# Power.net
KiCad netlist of a schematic drawn in Altium Designer
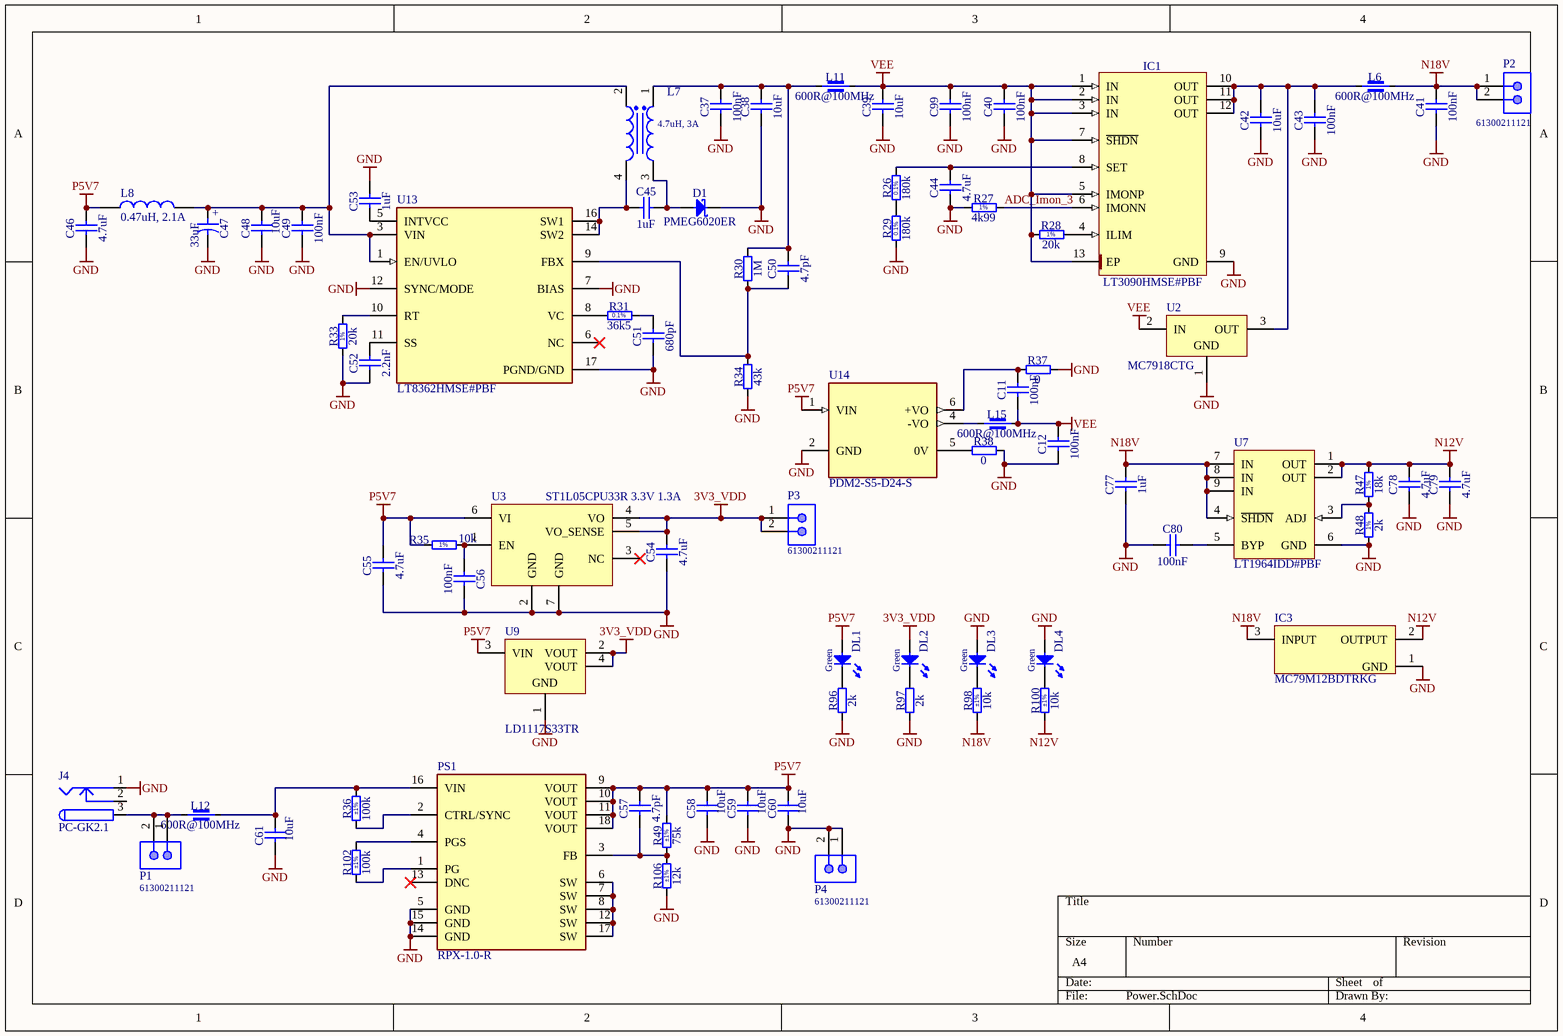
[diagram p0: Power.SchDoc]

(export (version "E")
  (design (tool "Eeschema 10.0.6"))
  (components
    (comp (ref "C11")
      (value "100nF")
      (footprint "CAPC1005X55N")
      (description "Non-polarised capacitor")
      (fields
        (field (name "PART NUMBER") "CC0402_100NF_16V_10%_X7R")
        (field (name "VOLTAGE") "16V")
        (field (name "AUTHOR") "CERN DEM JLC")
      )
      (libsource (lib "Capacitors") (part "Capacitor - non polarized"))
    )
    (comp (ref "C12")
      (value "100nF")
      (footprint "CAPC1005X55N")
      (description "Non-polarised capacitor")
      (fields
        (field (name "PART NUMBER") "CC0402_100NF_16V_10%_X7R")
        (field (name "VOLTAGE") "16V")
        (field (name "AUTHOR") "CERN DEM JLC")
      )
      (libsource (lib "Capacitors") (part "Capacitor - non polarized"))
    )
    (comp (ref "C37")
      (value "100nF")
      (footprint "CAPC1608X87N")
      (description "Non-polarised capacitor")
      (fields
        (field (name "PART NUMBER") "CC0603_100NF_50V_10%_X5R")
        (field (name "VOLTAGE") "50V")
        (field (name "AUTHOR") "CERN DEM MR")
      )
      (libsource (lib "Capacitors") (part "Capacitor - non polarized"))
    )
    (comp (ref "C38")
      (value "10uF")
      (footprint "CAPC3216X190N")
      (description "Non-polarised capacitor")
      (fields
        (field (name "PART NUMBER") "CC1206_10UF_35V_10%_X7R_YUDEN_GMJ316BB7106KLHT")
        (field (name "VOLTAGE") "35V")
        (field (name "AUTHOR") "CERN DEM BC")
      )
      (libsource (lib "Capacitors") (part "Capacitor - non polarized"))
    )
    (comp (ref "C39")
      (value "10uF")
      (footprint "CAPC3216X190N")
      (description "Non-polarised capacitor")
      (fields
        (field (name "PART NUMBER") "CC1206_10UF_35V_10%_X7R_YUDEN_GMJ316BB7106KLHT")
        (field (name "VOLTAGE") "35V")
        (field (name "AUTHOR") "CERN DEM BC")
      )
      (libsource (lib "Capacitors") (part "Capacitor - non polarized"))
    )
    (comp (ref "C40")
      (value "100nF")
      (footprint "CAPC1608X87N")
      (description "Non-polarised capacitor")
      (fields
        (field (name "PART NUMBER") "CC0603_100NF_50V_10%_X5R")
        (field (name "VOLTAGE") "50V")
        (field (name "AUTHOR") "CERN DEM MR")
      )
      (libsource (lib "Capacitors") (part "Capacitor - non polarized"))
    )
    (comp (ref "C41")
      (value "100nF")
      (footprint "CAPC1608X87N")
      (description "Non-polarised capacitor")
      (fields
        (field (name "PART NUMBER") "CC0603_100NF_50V_10%_X5R")
        (field (name "VOLTAGE") "50V")
        (field (name "AUTHOR") "CERN DEM MR")
      )
      (libsource (lib "Capacitors") (part "Capacitor - non polarized"))
    )
    (comp (ref "C42")
      (value "10uF")
      (footprint "CAPC3216X190N")
      (description "Non-polarised capacitor")
      (fields
        (field (name "PART NUMBER") "CC1206_10UF_35V_10%_X7R_YUDEN_GMJ316BB7106KLHT")
        (field (name "VOLTAGE") "35V")
        (field (name "AUTHOR") "CERN DEM BC")
      )
      (libsource (lib "Capacitors") (part "Capacitor - non polarized"))
    )
    (comp (ref "C43")
      (value "100nF")
      (footprint "CAPC1608X87N")
      (description "Non-polarised capacitor")
      (fields
        (field (name "PART NUMBER") "CC0603_100NF_50V_10%_X5R")
        (field (name "VOLTAGE") "50V")
        (field (name "AUTHOR") "CERN DEM MR")
      )
      (libsource (lib "Capacitors") (part "Capacitor - non polarized"))
    )
    (comp (ref "C44")
      (value "4.7uF")
      (footprint "CAPC1608X90N")
      (description "Non-polarised capacitor")
      (fields
        (field (name "PART NUMBER") "CC0603_4.7UF_25V_10%_X5R")
        (field (name "VOLTAGE") "25V")
        (field (name "AUTHOR") "CERN DEM JLC")
      )
      (libsource (lib "Capacitors") (part "Capacitor - non polarized"))
    )
    (comp (ref "C45")
      (value "1uF")
      (footprint "CAPC3216X140N")
      (description "Non-polarised capacitor")
      (fields
        (field (name "PART NUMBER") "CC1206_1UF_100V_10%_X7R")
        (field (name "VOLTAGE") "100V")
        (field (name "AUTHOR") "CERN DEM BC")
      )
      (libsource (lib "Capacitors") (part "Capacitor - non polarized"))
    )
    (comp (ref "C46")
      (value "4.7uF")
      (footprint "CAPC1608X90N")
      (description "Non-polarised capacitor")
      (fields
        (field (name "PART NUMBER") "CC0603_4.7UF_25V_10%_X5R")
        (field (name "VOLTAGE") "25V")
        (field (name "AUTHOR") "CERN DEM JLC")
      )
      (libsource (lib "Capacitors") (part "Capacitor - non polarized"))
    )
    (comp (ref "C47")
      (value "33uF")
      (footprint "CAPAE660X540N")
      (description "Polarised capacitor")
      (fields
        (field (name "PART NUMBER") "CAE660-540_33UF_35V_20%")
        (field (name "VOLTAGE") "35V")
        (field (name "AUTHOR") "CERN DEM JLC")
      )
      (libsource (lib "Capacitors") (part "Capacitor - polarized"))
    )
    (comp (ref "C48")
      (value "10uF")
      (footprint "CAPC3216X190N")
      (description "Non-polarised capacitor")
      (fields
        (field (name "PART NUMBER") "CC1206_10UF_35V_10%_X7R_YUDEN_GMJ316BB7106KLHT")
        (field (name "VOLTAGE") "35V")
        (field (name "AUTHOR") "CERN DEM BC")
      )
      (libsource (lib "Capacitors") (part "Capacitor - non polarized"))
    )
    (comp (ref "C49")
      (value "100nF")
      (footprint "CAPC1608X87N")
      (description "Non-polarised capacitor")
      (fields
        (field (name "PART NUMBER") "CC0603_100NF_50V_10%_X5R")
        (field (name "VOLTAGE") "50V")
        (field (name "AUTHOR") "CERN DEM MR")
      )
      (libsource (lib "Capacitors") (part "Capacitor - non polarized"))
    )
    (comp (ref "C50")
      (value "4.7pF")
      (footprint "CAPC1005X55N")
      (description "Non-polarised capacitor")
      (fields
        (field (name "PART NUMBER") "CC0402_4.7PF_50V_0.25PF_C0G")
        (field (name "VOLTAGE") "50V")
        (field (name "AUTHOR") "CERN DEM JLC")
      )
      (libsource (lib "Capacitors") (part "Capacitor - non polarized"))
    )
    (comp (ref "C51")
      (value "680pF")
      (footprint "CAPC1005X55N")
      (description "Non-polarised capacitor")
      (fields
        (field (name "PART NUMBER") "CC0402_680PF_50V_5%_X7R")
        (field (name "VOLTAGE") "50V")
        (field (name "AUTHOR") "CERN DEM JLC")
      )
      (libsource (lib "Capacitors") (part "Capacitor - non polarized"))
    )
    (comp (ref "C52")
      (value "2.2nF")
      (footprint "CAPC1005X55N")
      (description "Non-polarised capacitor")
      (fields
        (field (name "PART NUMBER") "CC0402_2.2NF_50V_10%_X7R")
        (field (name "VOLTAGE") "50V")
        (field (name "AUTHOR") "CERN DEM JLC")
      )
      (libsource (lib "Capacitors") (part "Capacitor - non polarized"))
    )
    (comp (ref "C53")
      (value "1uF")
      (footprint "CAPC1005X55N")
      (description "Non-polarised capacitor")
      (fields
        (field (name "PART NUMBER") "CC0402_1UF_16V_10%_X5R")
        (field (name "VOLTAGE") "16V")
        (field (name "AUTHOR") "CERN DEM JLC")
      )
      (libsource (lib "Capacitors") (part "Capacitor - non polarized"))
    )
    (comp (ref "C54")
      (value "4.7uF")
      (footprint "CAPC1709X95N")
      (description "Non-polarised capacitor")
      (fields
        (field (name "PART NUMBER") "CC0603_4.7UF_16V_10%_X5R")
        (field (name "VOLTAGE") "16V")
        (field (name "AUTHOR") "CERN DEM JLC")
      )
      (libsource (lib "Capacitors") (part "Capacitor - non polarized"))
    )
    (comp (ref "C55")
      (value "4.7uF")
      (footprint "CAPC1709X95N")
      (description "Non-polarised capacitor")
      (fields
        (field (name "PART NUMBER") "CC0603_4.7UF_16V_10%_X5R")
        (field (name "VOLTAGE") "16V")
        (field (name "AUTHOR") "CERN DEM JLC")
      )
      (libsource (lib "Capacitors") (part "Capacitor - non polarized"))
    )
    (comp (ref "C56")
      (value "100nF")
      (footprint "CAPC1005X55N")
      (description "Non-polarised capacitor")
      (fields
        (field (name "PART NUMBER") "CC0402_100NF_16V_10%_X5R")
        (field (name "VOLTAGE") "16V")
        (field (name "AUTHOR") "CERN DEM JLC")
      )
      (libsource (lib "Capacitors") (part "Capacitor - non polarized"))
    )
    (comp (ref "C57")
      (value "4.7pF")
      (footprint "CAPC1005X55N")
      (description "Non-polarised capacitor")
      (fields
        (field (name "PART NUMBER") "CC0402_4.7PF_50V_0.25PF_C0G")
        (field (name "VOLTAGE") "50V")
        (field (name "AUTHOR") "CERN DEM JLC")
      )
      (libsource (lib "Capacitors") (part "Capacitor - non polarized"))
    )
    (comp (ref "C58")
      (value "10uF")
      (footprint "CAPC3216X190N")
      (description "Non-polarised capacitor")
      (fields
        (field (name "PART NUMBER") "CC1206_10UF_35V_10%_X7R_YUDEN_GMJ316BB7106KLHT")
        (field (name "VOLTAGE") "35V")
        (field (name "AUTHOR") "CERN DEM BC")
      )
      (libsource (lib "Capacitors") (part "Capacitor - non polarized"))
    )
    (comp (ref "C59")
      (value "10uF")
      (footprint "CAPC3216X190N")
      (description "Non-polarised capacitor")
      (fields
        (field (name "PART NUMBER") "CC1206_10UF_35V_10%_X7R_YUDEN_GMJ316BB7106KLHT")
        (field (name "VOLTAGE") "35V")
        (field (name "AUTHOR") "CERN DEM BC")
      )
      (libsource (lib "Capacitors") (part "Capacitor - non polarized"))
    )
    (comp (ref "C60")
      (value "10uF")
      (footprint "CAPC3216X190N")
      (description "Non-polarised capacitor")
      (fields
        (field (name "PART NUMBER") "CC1206_10UF_35V_10%_X7R_YUDEN_GMJ316BB7106KLHT")
        (field (name "VOLTAGE") "35V")
        (field (name "AUTHOR") "CERN DEM BC")
      )
      (libsource (lib "Capacitors") (part "Capacitor - non polarized"))
    )
    (comp (ref "C61")
      (value "10uF")
      (footprint "CAPC3216X190N")
      (description "Non-polarised capacitor")
      (fields
        (field (name "PART NUMBER") "CC1206_10UF_35V_10%_X7R_YUDEN_GMJ316BB7106KLHT")
        (field (name "VOLTAGE") "35V")
        (field (name "AUTHOR") "CERN DEM BC")
      )
      (libsource (lib "Capacitors") (part "Capacitor - non polarized"))
    )
    (comp (ref "C77")
      (value "1uF")
      (footprint "CAPC1608X87N")
      (description "Non-polarised capacitor")
      (fields
        (field (name "PART NUMBER") "CC0603_1UF_25V_10%_X7R")
        (field (name "VOLTAGE") "25V")
        (field (name "AUTHOR") "CERN DEM JLC")
      )
      (libsource (lib "Capacitors") (part "Capacitor - non polarized"))
    )
    (comp (ref "C78")
      (value "4.7uF")
      (footprint "CAPC1709X95N")
      (description "Non-polarised capacitor")
      (fields
        (field (name "PART NUMBER") "CC0603_4.7UF_16V_10%_X5R")
        (field (name "VOLTAGE") "16V")
        (field (name "AUTHOR") "CERN DEM JLC")
      )
      (libsource (lib "Capacitors") (part "Capacitor - non polarized"))
    )
    (comp (ref "C79")
      (value "4.7uF")
      (footprint "CAPC1709X95N")
      (description "Non-polarised capacitor")
      (fields
        (field (name "PART NUMBER") "CC0603_4.7UF_16V_10%_X5R")
        (field (name "VOLTAGE") "16V")
        (field (name "AUTHOR") "CERN DEM JLC")
      )
      (libsource (lib "Capacitors") (part "Capacitor - non polarized"))
    )
    (comp (ref "C80")
      (value "100nF")
      (footprint "CAPC1005X55N")
      (description "Non-polarised capacitor")
      (fields
        (field (name "PART NUMBER") "CC0402_100NF_16V_10%_X7R")
        (field (name "VOLTAGE") "16V")
        (field (name "AUTHOR") "CERN DEM JLC")
      )
      (libsource (lib "Capacitors") (part "Capacitor - non polarized"))
    )
    (comp (ref "C99")
      (value "100nF")
      (footprint "CAPC1608X87N")
      (description "Non-polarised capacitor")
      (fields
        (field (name "PART NUMBER") "CC0603_100NF_50V_10%_X5R")
        (field (name "VOLTAGE") "50V")
        (field (name "AUTHOR") "CERN DEM MR")
      )
      (libsource (lib "Capacitors") (part "Capacitor - non polarized"))
    )
    (comp (ref "D1")
      (value "PMEG6020ER")
      (footprint "SODFL3517X110N")
      (description "Schottky Diode")
      (fields
        (field (name "VOLTAGE") "60V")
        (field (name "POWER") "2A")
        (field (name "AUTHOR") "CERN DEM JMW")
      )
      (libsource (lib "ICs And Semiconductors") (part "Diode Schottky"))
    )
    (comp (ref "DL1")
      (value "Green")
      (footprint "LED_OSRAM_LGL29K")
      (description "LED Green 1C 2A")
      (fields
        (field (name "PART NUMBER") "LED_OSRAM_LG L29K-G2J1-24-Z")
        (field (name "MANUFACTURER") "OSRAM")
        (field (name "AUTHOR") "CERN DEM JLC")
      )
      (libsource (lib "ICs And Semiconductors") (part "LED Green 1C 2A"))
    )
    (comp (ref "DL2")
      (value "Green")
      (footprint "LED_OSRAM_LGL29K")
      (description "LED Green 1C 2A")
      (fields
        (field (name "PART NUMBER") "LED_OSRAM_LG L29K-G2J1-24-Z")
        (field (name "MANUFACTURER") "OSRAM")
        (field (name "AUTHOR") "CERN DEM JLC")
      )
      (libsource (lib "ICs And Semiconductors") (part "LED Green 1C 2A"))
    )
    (comp (ref "DL3")
      (value "Green")
      (footprint "LED_OSRAM_LGL29K")
      (description "LED Green 1C 2A")
      (fields
        (field (name "PART NUMBER") "LED_OSRAM_LG L29K-G2J1-24-Z")
        (field (name "MANUFACTURER") "OSRAM")
        (field (name "AUTHOR") "CERN DEM JLC")
      )
      (libsource (lib "ICs And Semiconductors") (part "LED Green 1C 2A"))
    )
    (comp (ref "DL4")
      (value "Green")
      (footprint "LED_OSRAM_LGL29K")
      (description "LED Green 1C 2A")
      (fields
        (field (name "PART NUMBER") "LED_OSRAM_LG L29K-G2J1-24-Z")
        (field (name "MANUFACTURER") "OSRAM")
        (field (name "AUTHOR") "CERN DEM JLC")
      )
      (libsource (lib "ICs And Semiconductors") (part "LED Green 1C 2A"))
    )
    (comp (ref "IC1")
      (value "LT3090HMSE#PBF")
      (footprint "SOP65P490X110-13N-R175X294")
      (description "–36V, 600mA Negative Linear Regulator with Programmable Current Limit")
      (fields (field (name "MANUFACTURER") "LINEAR TECHNOLOGY") (field (name "AUTHOR") "CERN DEM JLC"))
      (libsource (lib "ICs And Semiconductors") (part "LT3090HMSE#PBF"))
    )
    (comp (ref "IC3")
      (value "MC79M12BDTRKG")
      (footprint "TO228P991X239-3N-R546X521")
      (libsource (lib "MG_lib_laptop") (part "MC79M12BDTRKG"))
    )
    (comp (ref "J4")
      (value "PC-GK2.1")
      (footprint "DC2020")
      (description "Low Voltage Power Supply Connector (maritex)")
      (fields (field (name "PUBLISHER") "Altium Limited"))
      (libsource (lib "LIBRARY_SCH") (part "CON_DC_JACK_TH"))
    )
    (comp (ref "L6")
      (value "600R@100MHz")
      (footprint "INDC2012X110N")
      (fields
        (field (name "PART NUMBER") "IND0805_WURTH_742792040")
        (field (name "POWER") "2A")
        (field (name "TOLERANCE") "±25%")
        (field (name "AUTHOR") "CERN DEM JLC")
      )
      (libsource (lib "Inductors & Transformers") (part "Ferrite Bead"))
    )
    (comp (ref "L7")
      (value "4.7uH, 3A")
      (footprint "WE-DD_1260")
      (description "WE-DD SMT Shielded Coupled Inductor, size 1260, 4.7uH, 3A")
      (fields
        (field (name "MANUFACTURER") "Wurth Elektronik")
        (field (name "MANUFACTURER PART NUMBER") "744871004")
      )
      (libsource (lib "744871470_Altium_WE-DD_rev20a") (part "744871004"))
    )
    (comp (ref "L8")
      (value "0.47uH, 2.1A")
      (footprint "WE-PMI_0806_H1")
      (description "WE-PMI Power Multilayer Inductor, size 0806, 0.47uH, 2.1A")
      (fields
        (field (name "MANUFACTURER") "Wurth Elektronik")
        (field (name "MANUFACTURER PART NUMBER") "74479876147")
      )
      (libsource (lib "Altium_WE-PMI_rev20a") (part "74479876147"))
    )
    (comp (ref "L11")
      (value "600R@100MHz")
      (footprint "INDC2012X110N")
      (fields
        (field (name "PART NUMBER") "IND0805_WURTH_742792040")
        (field (name "POWER") "2A")
        (field (name "TOLERANCE") "±25%")
        (field (name "AUTHOR") "CERN DEM JLC")
      )
      (libsource (lib "Inductors & Transformers") (part "Ferrite Bead"))
    )
    (comp (ref "L12")
      (value "600R@100MHz")
      (footprint "INDC2012X110N")
      (fields
        (field (name "PART NUMBER") "IND0805_WURTH_742792040")
        (field (name "POWER") "2A")
        (field (name "TOLERANCE") "±25%")
        (field (name "AUTHOR") "CERN DEM JLC")
      )
      (libsource (lib "Inductors & Transformers") (part "Ferrite Bead"))
    )
    (comp (ref "L15")
      (value "600R@100MHz")
      (footprint "INDC2012X110N")
      (fields
        (field (name "PART NUMBER") "IND0805_WURTH_742792040")
        (field (name "POWER") "2A")
        (field (name "TOLERANCE") "±25%")
        (field (name "AUTHOR") "CERN DEM JLC")
      )
      (libsource (lib "Inductors & Transformers") (part "Ferrite Bead"))
    )
    (comp (ref "P1")
      (value "61300211121")
      (footprint "61300211121")
      (description "WR-PHD Pin Header, THT, pitch 2.54mm, Single Row, Vertical, 2p")
      (fields (field (name "MANUFACTURER") "Wurth Elektronik"))
      (libsource (lib "o155175v243 Altium_WR-PHD (rev20a)") (part "61300211121"))
    )
    (comp (ref "P2")
      (value "61300211121")
      (footprint "61300211121")
      (description "WR-PHD Pin Header, THT, pitch 2.54mm, Single Row, Vertical, 2p")
      (fields (field (name "MANUFACTURER") "Wurth Elektronik"))
      (libsource (lib "o155175v243 Altium_WR-PHD (rev20a)") (part "61300211121"))
    )
    (comp (ref "P3")
      (value "61300211121")
      (footprint "61300211121")
      (description "WR-PHD Pin Header, THT, pitch 2.54mm, Single Row, Vertical, 2p")
      (fields (field (name "MANUFACTURER") "Wurth Elektronik"))
      (libsource (lib "o155175v243 Altium_WR-PHD (rev20a)") (part "61300211121"))
    )
    (comp (ref "P4")
      (value "61300211121")
      (footprint "61300211121")
      (description "WR-PHD Pin Header, THT, pitch 2.54mm, Single Row, Vertical, 2p")
      (fields (field (name "MANUFACTURER") "Wurth Elektronik"))
      (libsource (lib "o155175v243 Altium_WR-PHD (rev20a)") (part "61300211121"))
    )
    (comp (ref "PS1")
      (value "RPX-1.0-R")
      (footprint "SamacSys:RPX10R")
      (description "Power Supply")
      (libsource (lib "SamacSys") (part "RPX-1.0-R"))
    )
    (comp (ref "R26")
      (value "180k")
      (footprint "RESC3216X65N")
      (description "Resistor - 0.1%")
      (fields
        (field (name "PART NUMBER") "R1206_180K_0.1%_0.25W_25PPM")
        (field (name "POWER") "0.25W")
        (field (name "AUTHOR") "CERN DEM JLC")
      )
      (libsource (lib "Resistors") (part "Resistor - 0.1%"))
    )
    (comp (ref "R27")
      (value "4k99")
      (footprint "RESC1608X55N")
      (description "Resistor - 1%")
      (fields
        (field (name "PART NUMBER") "R0603_4K99_1%_0.063W_50PPM")
        (field (name "POWER") "0.063W")
        (field (name "AUTHOR") "CERN DEM JLC")
      )
      (libsource (lib "Resistors") (part "Resistor - 1%"))
    )
    (comp (ref "R28")
      (value "20k")
      (footprint "RESC1005X40N")
      (description "Resistor - 1%")
      (fields
        (field (name "PART NUMBER") "R0402_20K_1%_0.0625W_100PPM")
        (field (name "POWER") "0.0625W")
        (field (name "AUTHOR") "CERN DEM JLC")
      )
      (libsource (lib "Resistors") (part "Resistor - 1%"))
    )
    (comp (ref "R29")
      (value "180k")
      (footprint "RESC3216X65N")
      (description "Resistor - 0.1%")
      (fields
        (field (name "PART NUMBER") "R1206_180K_0.1%_0.25W_25PPM")
        (field (name "POWER") "0.25W")
        (field (name "AUTHOR") "CERN DEM JLC")
      )
      (libsource (lib "Resistors") (part "Resistor - 0.1%"))
    )
    (comp (ref "R30")
      (value "1M")
      (footprint "RESC1005X40N")
      (description "Resistor - 1%")
      (fields
        (field (name "PART NUMBER") "R0402_1M_1%_0.0625W_100PPM")
        (field (name "POWER") "0.0625W")
        (field (name "AUTHOR") "CERN DEM JLC")
      )
      (libsource (lib "") (part "Resistor - 1%_1"))
    )
    (comp (ref "R31")
      (value "36k5")
      (footprint "RESC1608X55N")
      (description "Resistor - 0.1%")
      (fields
        (field (name "PART NUMBER") "R0603_36K5_0.1%_0.063W_10PPM")
        (field (name "POWER") "0.063W")
        (field (name "AUTHOR") "CERN DEM JLC")
      )
      (libsource (lib "Resistors") (part "Resistor - 0.1%"))
    )
    (comp (ref "R33")
      (value "20k")
      (footprint "RESC1005X40N")
      (description "Resistor - 1%")
      (fields
        (field (name "PART NUMBER") "R0402_20K_1%_0.0625W_100PPM")
        (field (name "POWER") "0.0625W")
        (field (name "AUTHOR") "CERN DEM JLC")
      )
      (libsource (lib "Resistors") (part "Resistor - 1%"))
    )
    (comp (ref "R34")
      (value "43k")
      (footprint "RESC1005X40N")
      (description "Resistor - 1%")
      (fields
        (field (name "PART NUMBER") "R0402_43K_1%_0.0625W_100PPM")
        (field (name "POWER") "0.0625W")
        (field (name "AUTHOR") "CERN DEM JLC")
      )
      (libsource (lib "") (part "Resistor - 1%_1"))
    )
    (comp (ref "R35")
      (value "10k")
      (footprint "RESC1005X40N")
      (description "Resistor - 1%")
      (fields
        (field (name "PART NUMBER") "R0402_10K_1%_0.0625W_100PPM")
        (field (name "POWER") "0.0625W")
        (field (name "AUTHOR") "CERN DEM JLC")
      )
      (libsource (lib "Resistors") (part "Resistor - 1%"))
    )
    (comp (ref "R36")
      (value "100k")
      (footprint "RESC1005X40N")
      (description "Resistor - 1%")
      (fields
        (field (name "TOLERANCE") "±1%")
        (field (name "PART NUMBER") "R0402_100K_1%_0.0625W_100PPM")
        (field (name "POWER") "0.0625W")
        (field (name "AUTHOR") "CERN DEM JLC")
      )
      (libsource (lib "") (part "Resistor - 1%_1"))
    )
    (comp (ref "R37")
      (value "0")
      (footprint "RESC2012X60N")
      (description "Resistor")
      (fields
        (field (name "PART NUMBER") "R0805_0R_JUMPER")
        (field (name "MANUFACTURER") "GENERIC")
        (field (name "AUTHOR") "CERN DEM JLC")
      )
      (libsource (lib "Resistors") (part "Resistor"))
    )
    (comp (ref "R38")
      (value "0")
      (footprint "RESC2012X60N")
      (description "Resistor")
      (fields
        (field (name "PART NUMBER") "R0805_0R_JUMPER")
        (field (name "MANUFACTURER") "GENERIC")
        (field (name "AUTHOR") "CERN DEM JLC")
      )
      (libsource (lib "Resistors") (part "Resistor"))
    )
    (comp (ref "R47")
      (value "18k")
      (footprint "RESC1005X40N")
      (description "Resistor - 1%")
      (fields
        (field (name "PART NUMBER") "R0402_18K_1%_0.0625W_100PPM")
        (field (name "POWER") "0.0625W")
        (field (name "AUTHOR") "CERN DEM JLC")
      )
      (libsource (lib "Resistors") (part "Resistor - 1%"))
    )
    (comp (ref "R48")
      (value "2k")
      (footprint "RESC1005X40N")
      (description "Resistor - 1%")
      (fields
        (field (name "PART NUMBER") "R0402_2K_1%_0.0625W_100PPM")
        (field (name "POWER") "0.0625W")
        (field (name "AUTHOR") "CERN DEM JLC")
      )
      (libsource (lib "Resistors") (part "Resistor - 1%"))
    )
    (comp (ref "R49")
      (value "75k")
      (footprint "RESC1005X40N")
      (description "Resistor - 1%")
      (fields
        (field (name "TOLERANCE") "±1%")
        (field (name "PART NUMBER") "R0402_75K_1%_0.0625W_100PPM")
        (field (name "POWER") "0.0625W")
        (field (name "AUTHOR") "CERN DEM JLC")
      )
      (libsource (lib "") (part "Resistor - 1%_1"))
    )
    (comp (ref "R96")
      (value "2k")
      (footprint "RESC1005X40N")
      (description "Resistor - 1%")
      (fields
        (field (name "PART NUMBER") "R0402_2K_1%_0.0625W_100PPM")
        (field (name "POWER") "0.0625W")
        (field (name "AUTHOR") "CERN DEM JLC")
      )
      (libsource (lib "") (part "Resistor - 1%_1"))
    )
    (comp (ref "R97")
      (value "2k")
      (footprint "RESC1005X40N")
      (description "Resistor - 1%")
      (fields
        (field (name "PART NUMBER") "R0402_2K_1%_0.0625W_100PPM")
        (field (name "POWER") "0.0625W")
        (field (name "AUTHOR") "CERN DEM JLC")
      )
      (libsource (lib "") (part "Resistor - 1%_1"))
    )
    (comp (ref "R98")
      (value "10k")
      (footprint "RESC1005X40N")
      (description "Resistor - 1%")
      (fields
        (field (name "TOLERANCE") "±1%")
        (field (name "PART NUMBER") "R0402_10K_1%_0.0625W_100PPM")
        (field (name "POWER") "0.0625W")
        (field (name "AUTHOR") "CERN DEM JLC")
      )
      (libsource (lib "") (part "Resistor - 1%_1"))
    )
    (comp (ref "R100")
      (value "10k")
      (footprint "RESC1005X40N")
      (description "Resistor - 1%")
      (fields
        (field (name "TOLERANCE") "±1%")
        (field (name "PART NUMBER") "R0402_10K_1%_0.0625W_100PPM")
        (field (name "POWER") "0.0625W")
        (field (name "AUTHOR") "CERN DEM JLC")
      )
      (libsource (lib "") (part "Resistor - 1%_1"))
    )
    (comp (ref "R102")
      (value "100k")
      (footprint "RESC1005X40N")
      (description "Resistor - 1%")
      (fields
        (field (name "TOLERANCE") "±1%")
        (field (name "PART NUMBER") "R0402_100K_1%_0.0625W_100PPM")
        (field (name "POWER") "0.0625W")
        (field (name "AUTHOR") "CERN DEM JLC")
      )
      (libsource (lib "") (part "Resistor - 1%_1"))
    )
    (comp (ref "R106")
      (value "12k")
      (footprint "RESC1005X40N")
      (description "Resistor - 1%")
      (fields
        (field (name "TOLERANCE") "±1%")
        (field (name "PART NUMBER") "R0402_12K_1%_0.0625W_100PPM")
        (field (name "POWER") "0.0625W")
        (field (name "AUTHOR") "CERN DEM JLC")
      )
      (libsource (lib "") (part "Resistor - 1%_1"))
    )
    (comp (ref "U2")
      (value "MC7918CTG")
      (footprint "TO-220")
      (description "Negative Voltage Regulator, -15V, 3-Pin D2PAK")
      (libsource (lib "Altium Content Vault") (part "PM-REG-7905-SIL3"))
    )
    (comp (ref "U3")
      (value "ST1L05CPU33R 3.3V 1.3A")
      (footprint "SON95P300X300X80-7N-R160X240")
      (description "LDO, 3.3V, 1.3A, Very low quiescent current BiCMOS voltage regulator")
      (fields
        (field (name "INTERNAL_PART_NUMBER") "MCD-01025")
        (field (name "MANUFACTURER_PART_NUMBER") "ST1L05CPU33R")
        (field (name "PROVIDED_BY") "SUBCO with ST control")
      )
      (libsource (lib "MCD_PARTS_database") (part "ST1L05CPU33R"))
    )
    (comp (ref "U7")
      (value "LT1964IDD#PBF")
      (footprint "LT-DD-8_V")
      (fields (field (name "MANUFACTURER") "Linear Technology"))
      (libsource (lib "Altium Content Vault") (part "LT-LT1964-DD-8"))
    )
    (comp (ref "U9")
      (value "LD1117S33TR")
      (footprint "SOT-223_L")
      (description "Fixed Low Drop Positive Voltage Regulator, 3.3V, 4-Pin SOT-223, Tape and Reel")
      (libsource (lib "Altium Content Vault") (part "PM-REG-LD1117-SOT4"))
    )
    (comp (ref "U13")
      (value "LT8362HMSE#PBF")
      (footprint "FP-MSE-16-05-08-1871-MFG")
      (description "IC REG BST SEPIC 2A 16MSOP")
      (libsource (lib "Altium Content Vault") (part "596e534f5bc6aab0301c228648d3e33"))
    )
    (comp (ref "U14")
      (value "PDM2-S5-D24-S")
      (footprint "CONV_PDM2-S5-D24-S")
      (fields (field (name "DIGI-KEY_PART_NUMBER") "102-3005-5-ND") (field (name "MF") "CUI Inc."))
      (libsource (lib "PDM2-S5-D24-S") (part "PDM2-S5-D24-S"))
    )
  )
  (nets
    (net (code "1") (name "/ADC_Imon_3") (class "Default")
      (node (ref "IC1") (pin "6") (pinfunction "IMONN_6") (pintype "input"))
      (node (ref "R27") (pin "2") (pinfunction "2_2") (pintype "passive"))
    )
    (net (code "2") (name "3V3_VDD") (class "Default")
      (node (ref "C54") (pin "2") (pinfunction "2_2") (pintype "passive"))
      (node (ref "DL2") (pin "2") (pinfunction "A_2") (pintype "passive"))
      (node (ref "P3") (pin "1") (pinfunction "1_1") (pintype "passive"))
      (node (ref "P3") (pin "2") (pinfunction "2_2") (pintype "passive"))
      (node (ref "U3") (pin "4") (pinfunction "VO_4") (pintype "passive"))
      (node (ref "U3") (pin "5") (pinfunction "VO_SENSE_5") (pintype "passive"))
      (node (ref "U9") (pin "2") (pinfunction "VOUT_2") (pintype "power_in"))
      (node (ref "U9") (pin "4") (pinfunction "VOUT_4") (pintype "power_in"))
    )
    (net (code "3") (name "GND") (class "Default")
      (node (ref "C12") (pin "1") (pinfunction "1_1") (pintype "passive"))
      (node (ref "C37") (pin "1") (pinfunction "1_1") (pintype "passive"))
      (node (ref "C38") (pin "1") (pinfunction "1_1") (pintype "passive"))
      (node (ref "C39") (pin "1") (pinfunction "1_1") (pintype "passive"))
      (node (ref "C40") (pin "1") (pinfunction "1_1") (pintype "passive"))
      (node (ref "C41") (pin "1") (pinfunction "1_1") (pintype "passive"))
      (node (ref "C42") (pin "1") (pinfunction "1_1") (pintype "passive"))
      (node (ref "C43") (pin "1") (pinfunction "1_1") (pintype "passive"))
      (node (ref "C44") (pin "1") (pinfunction "1_1") (pintype "passive"))
      (node (ref "C46") (pin "1") (pinfunction "1_1") (pintype "passive"))
      (node (ref "C47") (pin "2") (pinfunction "2_2") (pintype "passive"))
      (node (ref "C48") (pin "1") (pinfunction "1_1") (pintype "passive"))
      (node (ref "C49") (pin "1") (pinfunction "1_1") (pintype "passive"))
      (node (ref "C51") (pin "1") (pinfunction "1_1") (pintype "passive"))
      (node (ref "C52") (pin "1") (pinfunction "1_1") (pintype "passive"))
      (node (ref "C53") (pin "2") (pinfunction "2_2") (pintype "passive"))
      (node (ref "C54") (pin "1") (pinfunction "1_1") (pintype "passive"))
      (node (ref "C55") (pin "1") (pinfunction "1_1") (pintype "passive"))
      (node (ref "C56") (pin "1") (pinfunction "1_1") (pintype "passive"))
      (node (ref "C58") (pin "1") (pinfunction "1_1") (pintype "passive"))
      (node (ref "C59") (pin "1") (pinfunction "1_1") (pintype "passive"))
      (node (ref "C60") (pin "1") (pinfunction "1_1") (pintype "passive"))
      (node (ref "C61") (pin "1") (pinfunction "1_1") (pintype "passive"))
      (node (ref "C77") (pin "1") (pinfunction "1_1") (pintype "passive"))
      (node (ref "C78") (pin "1") (pinfunction "1_1") (pintype "passive"))
      (node (ref "C79") (pin "1") (pinfunction "1_1") (pintype "passive"))
      (node (ref "C80") (pin "1") (pinfunction "1_1") (pintype "passive"))
      (node (ref "C99") (pin "1") (pinfunction "1_1") (pintype "passive"))
      (node (ref "D1") (pin "1") (pinfunction "C_1") (pintype "passive"))
      (node (ref "DL3") (pin "2") (pinfunction "A_2") (pintype "passive"))
      (node (ref "DL4") (pin "2") (pinfunction "A_2") (pintype "passive"))
      (node (ref "IC1") (pin "9") (pinfunction "GND_9") (pintype "power_in"))
      (node (ref "IC3") (pin "1") (pinfunction "GND_1") (pintype "passive"))
      (node (ref "J4") (pin "1") (pintype "power_in"))
      (node (ref "P4") (pin "1") (pinfunction "1_1") (pintype "passive"))
      (node (ref "P4") (pin "2") (pinfunction "2_2") (pintype "passive"))
      (node (ref "PS1") (pin "14") (pinfunction "GND_14") (pintype "passive"))
      (node (ref "PS1") (pin "15") (pinfunction "GND_15") (pintype "passive"))
      (node (ref "PS1") (pin "5") (pinfunction "GND_5") (pintype "passive"))
      (node (ref "R106") (pin "1") (pinfunction "1_1") (pintype "passive"))
      (node (ref "R27") (pin "1") (pinfunction "1_1") (pintype "passive"))
      (node (ref "R29") (pin "1") (pinfunction "1_1") (pintype "passive"))
      (node (ref "R33") (pin "1") (pinfunction "1_1") (pintype "passive"))
      (node (ref "R34") (pin "1") (pinfunction "1_1") (pintype "passive"))
      (node (ref "R37") (pin "2") (pinfunction "2_2") (pintype "passive"))
      (node (ref "R38") (pin "2") (pinfunction "2_2") (pintype "passive"))
      (node (ref "R48") (pin "1") (pinfunction "1_1") (pintype "passive"))
      (node (ref "R96") (pin "1") (pinfunction "1_1") (pintype "passive"))
      (node (ref "R97") (pin "1") (pinfunction "1_1") (pintype "passive"))
      (node (ref "U13") (pin "12") (pinfunction "SYNC/MODE_12") (pintype "passive"))
      (node (ref "U13") (pin "17") (pinfunction "PGND/GND_17") (pintype "power_in"))
      (node (ref "U13") (pin "7") (pinfunction "BIAS_7") (pintype "passive"))
      (node (ref "U14") (pin "2") (pinfunction "GND_2") (pintype "power_in"))
      (node (ref "U2") (pin "1") (pinfunction "GND_1") (pintype "power_in"))
      (node (ref "U3") (pin "2") (pinfunction "GND_2") (pintype "passive"))
      (node (ref "U3") (pin "7") (pinfunction "GND_7") (pintype "passive"))
      (node (ref "U7") (pin "6") (pinfunction "GND_6") (pintype "power_in"))
      (node (ref "U9") (pin "1") (pinfunction "GND_1") (pintype "power_in"))
    )
    (net (code "4") (name "N12V") (class "Default")
      (node (ref "C78") (pin "2") (pinfunction "2_2") (pintype "passive"))
      (node (ref "C79") (pin "2") (pinfunction "2_2") (pintype "passive"))
      (node (ref "IC3") (pin "2") (pinfunction "OUTPUT_2") (pintype "passive"))
      (node (ref "R100") (pin "1") (pinfunction "1_1") (pintype "passive"))
      (node (ref "R47") (pin "2") (pinfunction "2_2") (pintype "passive"))
      (node (ref "U7") (pin "1") (pinfunction "OUT_1") (pintype "power_in"))
      (node (ref "U7") (pin "2") (pinfunction "OUT_2") (pintype "power_in"))
    )
    (net (code "5") (name "N18V") (class "Default")
      (node (ref "C41") (pin "2") (pinfunction "2_2") (pintype "passive"))
      (node (ref "C77") (pin "2") (pinfunction "2_2") (pintype "passive"))
      (node (ref "IC3") (pin "3") (pinfunction "INPUT_3") (pintype "passive"))
      (node (ref "L6") (pin "2") (pinfunction "2_2") (pintype "passive"))
      (node (ref "P2") (pin "1") (pinfunction "1_1") (pintype "passive"))
      (node (ref "P2") (pin "2") (pinfunction "2_2") (pintype "passive"))
      (node (ref "R98") (pin "1") (pinfunction "1_1") (pintype "passive"))
      (node (ref "U7") (pin "4") (pinfunction "~{SHDN}_4") (pintype "input"))
      (node (ref "U7") (pin "7") (pinfunction "IN_7") (pintype "power_in"))
      (node (ref "U7") (pin "8") (pinfunction "IN_8") (pintype "power_in"))
      (node (ref "U7") (pin "9") (pinfunction "IN_9") (pintype "power_in"))
    )
    (net (code "6") (name "Net-(C37-Pad2)") (class "Default")
      (node (ref "C37") (pin "2") (pinfunction "2_2") (pintype "passive"))
      (node (ref "C38") (pin "2") (pinfunction "2_2") (pintype "passive"))
      (node (ref "C50") (pin "2") (pinfunction "2_2") (pintype "passive"))
      (node (ref "L11") (pin "1") (pinfunction "1_1") (pintype "passive"))
      (node (ref "L7") (pin "1") (pinfunction "1_1") (pintype "passive"))
      (node (ref "R30") (pin "2") (pinfunction "2_2") (pintype "passive"))
    )
    (net (code "7") (name "Net-(C51-Pad2)") (class "Default")
      (node (ref "C51") (pin "2") (pinfunction "2_2") (pintype "passive"))
      (node (ref "R31") (pin "2") (pinfunction "2_2") (pintype "passive"))
    )
    (net (code "8") (name "Net-(D1-A)") (class "Default")
      (node (ref "C45") (pin "2") (pinfunction "2_2") (pintype "passive"))
      (node (ref "D1") (pin "2") (pinfunction "A_2") (pintype "passive"))
      (node (ref "L7") (pin "3") (pinfunction "3_3") (pintype "passive"))
    )
    (net (code "9") (name "Net-(DL1-C)") (class "Default")
      (node (ref "DL1") (pin "1") (pinfunction "C_1") (pintype "passive"))
      (node (ref "R96") (pin "2") (pinfunction "2_2") (pintype "passive"))
    )
    (net (code "10") (name "Net-(DL2-C)") (class "Default")
      (node (ref "DL2") (pin "1") (pinfunction "C_1") (pintype "passive"))
      (node (ref "R97") (pin "2") (pinfunction "2_2") (pintype "passive"))
    )
    (net (code "11") (name "Net-(DL3-C)") (class "Default")
      (node (ref "DL3") (pin "1") (pinfunction "C_1") (pintype "passive"))
      (node (ref "R98") (pin "2") (pinfunction "2_2") (pintype "passive"))
    )
    (net (code "12") (name "Net-(DL4-C)") (class "Default")
      (node (ref "DL4") (pin "1") (pinfunction "C_1") (pintype "passive"))
      (node (ref "R100") (pin "2") (pinfunction "2_2") (pintype "passive"))
    )
    (net (code "13") (name "Net-(IC1-ILIM)") (class "Default")
      (node (ref "IC1") (pin "4") (pinfunction "ILIM_4") (pintype "input"))
      (node (ref "R28") (pin "2") (pinfunction "2_2") (pintype "passive"))
    )
    (net (code "14") (name "Net-(IC1-SET)") (class "Default")
      (node (ref "C44") (pin "2") (pinfunction "2_2") (pintype "passive"))
      (node (ref "IC1") (pin "8") (pinfunction "SET_8") (pintype "input"))
      (node (ref "R26") (pin "2") (pinfunction "2_2") (pintype "passive"))
    )
    (net (code "15") (name "Net-(J4-Pad3)") (class "Default")
      (node (ref "J4") (pin "3") (pintype "power_in"))
      (node (ref "L12") (pin "1") (pinfunction "1_1") (pintype "passive"))
      (node (ref "P1") (pin "1") (pinfunction "1_1") (pintype "passive"))
      (node (ref "P1") (pin "2") (pinfunction "2_2") (pintype "passive"))
    )
    (net (code "16") (name "Net-(PS1-CTRL{slash}SYNC)") (class "Default")
      (node (ref "PS1") (pin "2") (pinfunction "CTRL/SYNC_2") (pintype "passive"))
      (node (ref "R36") (pin "1") (pinfunction "1_1") (pintype "passive"))
    )
    (net (code "17") (name "Net-(PS1-FB)") (class "Default")
      (node (ref "C57") (pin "1") (pinfunction "1_1") (pintype "passive"))
      (node (ref "PS1") (pin "3") (pinfunction "FB_3") (pintype "passive"))
      (node (ref "R106") (pin "2") (pinfunction "2_2") (pintype "passive"))
      (node (ref "R49") (pin "1") (pinfunction "1_1") (pintype "passive"))
    )
    (net (code "18") (name "Net-(PS1-PG)") (class "Default")
      (node (ref "PS1") (pin "1") (pinfunction "PG_1") (pintype "passive"))
      (node (ref "R102") (pin "1") (pinfunction "1_1") (pintype "passive"))
    )
    (net (code "19") (name "Net-(PS1-PGS)") (class "Default")
      (node (ref "PS1") (pin "4") (pinfunction "PGS_4") (pintype "passive"))
      (node (ref "R102") (pin "2") (pinfunction "2_2") (pintype "passive"))
    )
    (net (code "20") (name "Net-(PS1-SW-Pad12)") (class "Default")
      (node (ref "PS1") (pin "12") (pinfunction "SW_12") (pintype "passive"))
      (node (ref "PS1") (pin "17") (pinfunction "SW_17") (pintype "passive"))
      (node (ref "PS1") (pin "6") (pinfunction "SW_6") (pintype "passive"))
      (node (ref "PS1") (pin "7") (pinfunction "SW_7") (pintype "passive"))
      (node (ref "PS1") (pin "8") (pinfunction "SW_8") (pintype "passive"))
    )
    (net (code "21") (name "Net-(PS1-VIN)") (class "Default")
      (node (ref "C61") (pin "2") (pinfunction "2_2") (pintype "passive"))
      (node (ref "L12") (pin "2") (pinfunction "2_2") (pintype "passive"))
      (node (ref "PS1") (pin "16") (pinfunction "VIN_16") (pintype "passive"))
      (node (ref "R36") (pin "2") (pinfunction "2_2") (pintype "passive"))
    )
    (net (code "22") (name "Net-(R26-Pad1)") (class "Default")
      (node (ref "R26") (pin "1") (pinfunction "1_1") (pintype "passive"))
      (node (ref "R29") (pin "2") (pinfunction "2_2") (pintype "passive"))
    )
    (net (code "23") (name "Net-(U2-OUT)") (class "Default")
      (node (ref "C42") (pin "2") (pinfunction "2_2") (pintype "passive"))
      (node (ref "C43") (pin "2") (pinfunction "2_2") (pintype "passive"))
      (node (ref "IC1") (pin "10") (pinfunction "OUT_10") (pintype "power_in"))
      (node (ref "IC1") (pin "11") (pinfunction "OUT_11") (pintype "power_in"))
      (node (ref "IC1") (pin "12") (pinfunction "OUT_12") (pintype "power_in"))
      (node (ref "L6") (pin "1") (pinfunction "1_1") (pintype "passive"))
      (node (ref "U2") (pin "3") (pinfunction "OUT_3") (pintype "power_in"))
    )
    (net (code "24") (name "Net-(U3-EN)") (class "Default")
      (node (ref "C56") (pin "2") (pinfunction "2_2") (pintype "passive"))
      (node (ref "R35") (pin "2") (pinfunction "2_2") (pintype "passive"))
      (node (ref "U3") (pin "1") (pinfunction "EN_1") (pintype "passive"))
    )
    (net (code "25") (name "Net-(U7-ADJ)") (class "Default")
      (node (ref "R47") (pin "1") (pinfunction "1_1") (pintype "passive"))
      (node (ref "R48") (pin "2") (pinfunction "2_2") (pintype "passive"))
      (node (ref "U7") (pin "3") (pinfunction "ADJ_3") (pintype "input"))
    )
    (net (code "26") (name "Net-(U7-BYP)") (class "Default")
      (node (ref "C80") (pin "2") (pinfunction "2_2") (pintype "passive"))
      (node (ref "U7") (pin "5") (pinfunction "BYP_5") (pintype "passive"))
    )
    (net (code "27") (name "Net-(U13-EN{slash}UVLO)") (class "Default")
      (node (ref "C47") (pin "1") (pinfunction "1_1") (pintype "passive"))
      (node (ref "C48") (pin "2") (pinfunction "2_2") (pintype "passive"))
      (node (ref "C49") (pin "2") (pinfunction "2_2") (pintype "passive"))
      (node (ref "L7") (pin "2") (pinfunction "2_2") (pintype "passive"))
      (node (ref "L8") (pin "2") (pinfunction "2_2") (pintype "passive"))
      (node (ref "U13") (pin "1") (pinfunction "EN/UVLO_1") (pintype "input"))
      (node (ref "U13") (pin "3") (pinfunction "VIN_3") (pintype "power_in"))
    )
    (net (code "28") (name "Net-(U13-FBX)") (class "Default")
      (node (ref "C50") (pin "1") (pinfunction "1_1") (pintype "passive"))
      (node (ref "R30") (pin "1") (pinfunction "1_1") (pintype "passive"))
      (node (ref "R34") (pin "2") (pinfunction "2_2") (pintype "passive"))
      (node (ref "U13") (pin "9") (pinfunction "FBX_9") (pintype "passive"))
    )
    (net (code "29") (name "Net-(U13-INTVCC)") (class "Default")
      (node (ref "C53") (pin "1") (pinfunction "1_1") (pintype "passive"))
      (node (ref "U13") (pin "5") (pinfunction "INTVCC_5") (pintype "power_in"))
    )
    (net (code "30") (name "Net-(U13-RT)") (class "Default")
      (node (ref "R33") (pin "2") (pinfunction "2_2") (pintype "passive"))
      (node (ref "U13") (pin "10") (pinfunction "RT_10") (pintype "passive"))
    )
    (net (code "31") (name "Net-(U13-SS)") (class "Default")
      (node (ref "C52") (pin "2") (pinfunction "2_2") (pintype "passive"))
      (node (ref "U13") (pin "11") (pinfunction "SS_11") (pintype "passive"))
    )
    (net (code "32") (name "Net-(U13-SW1)") (class "Default")
      (node (ref "C45") (pin "1") (pinfunction "1_1") (pintype "passive"))
      (node (ref "L7") (pin "4") (pinfunction "4_4") (pintype "passive"))
      (node (ref "U13") (pin "14") (pinfunction "SW2_14") (pintype "passive"))
      (node (ref "U13") (pin "16") (pinfunction "SW1_16") (pintype "passive"))
    )
    (net (code "33") (name "Net-(U13-VC)") (class "Default")
      (node (ref "R31") (pin "1") (pinfunction "1_1") (pintype "passive"))
      (node (ref "U13") (pin "8") (pinfunction "VC_8") (pintype "power_in"))
    )
    (net (code "34") (name "Net-(U14-+VO)") (class "Default")
      (node (ref "C11") (pin "2") (pinfunction "2_2") (pintype "passive"))
      (node (ref "R37") (pin "1") (pinfunction "1_1") (pintype "passive"))
      (node (ref "U14") (pin "6") (pinfunction "+VO_6") (pintype "output"))
    )
    (net (code "35") (name "Net-(U14--VO)") (class "Default")
      (node (ref "L15") (pin "1") (pinfunction "1_1") (pintype "passive"))
      (node (ref "U14") (pin "4") (pinfunction "-VO_4") (pintype "output"))
    )
    (net (code "36") (name "Net-(U14-0V)") (class "Default")
      (node (ref "R38") (pin "1") (pinfunction "1_1") (pintype "passive"))
      (node (ref "U14") (pin "5") (pinfunction "0V_5") (pintype "power_in"))
    )
    (net (code "37") (name "P5V7") (class "Default")
      (node (ref "C46") (pin "2") (pinfunction "2_2") (pintype "passive"))
      (node (ref "C55") (pin "2") (pinfunction "2_2") (pintype "passive"))
      (node (ref "C57") (pin "2") (pinfunction "2_2") (pintype "passive"))
      (node (ref "C58") (pin "2") (pinfunction "2_2") (pintype "passive"))
      (node (ref "C59") (pin "2") (pinfunction "2_2") (pintype "passive"))
      (node (ref "C60") (pin "2") (pinfunction "2_2") (pintype "passive"))
      (node (ref "DL1") (pin "2") (pinfunction "A_2") (pintype "passive"))
      (node (ref "L8") (pin "1") (pinfunction "1_1") (pintype "passive"))
      (node (ref "PS1") (pin "10") (pinfunction "VOUT_10") (pintype "passive"))
      (node (ref "PS1") (pin "11") (pinfunction "VOUT_11") (pintype "passive"))
      (node (ref "PS1") (pin "18") (pinfunction "VOUT_18") (pintype "passive"))
      (node (ref "PS1") (pin "9") (pinfunction "VOUT_9") (pintype "passive"))
      (node (ref "R35") (pin "1") (pinfunction "1_1") (pintype "passive"))
      (node (ref "R49") (pin "2") (pinfunction "2_2") (pintype "passive"))
      (node (ref "U14") (pin "1") (pinfunction "VIN_1") (pintype "input"))
      (node (ref "U3") (pin "6") (pinfunction "VI_6") (pintype "passive"))
      (node (ref "U9") (pin "3") (pinfunction "VIN_3") (pintype "power_in"))
    )
    (net (code "38") (name "VEE") (class "Default")
      (node (ref "C11") (pin "1") (pinfunction "1_1") (pintype "passive"))
      (node (ref "C12") (pin "2") (pinfunction "2_2") (pintype "passive"))
      (node (ref "C39") (pin "2") (pinfunction "2_2") (pintype "passive"))
      (node (ref "C40") (pin "2") (pinfunction "2_2") (pintype "passive"))
      (node (ref "C99") (pin "2") (pinfunction "2_2") (pintype "passive"))
      (node (ref "IC1") (pin "1") (pinfunction "IN_1") (pintype "input"))
      (node (ref "IC1") (pin "13") (pinfunction "EP_13") (pintype "power_in"))
      (node (ref "IC1") (pin "2") (pinfunction "IN_2") (pintype "input"))
      (node (ref "IC1") (pin "3") (pinfunction "IN_3") (pintype "input"))
      (node (ref "IC1") (pin "5") (pinfunction "IMONP_5") (pintype "input"))
      (node (ref "IC1") (pin "7") (pinfunction "~{SHDN}_7") (pintype "input"))
      (node (ref "L11") (pin "2") (pinfunction "2_2") (pintype "passive"))
      (node (ref "L15") (pin "2") (pinfunction "2_2") (pintype "passive"))
      (node (ref "R28") (pin "1") (pinfunction "1_1") (pintype "passive"))
      (node (ref "U2") (pin "2") (pinfunction "IN_2") (pintype "power_in"))
    )
    (net (code "39") (name "unconnected-(J4-Pad2)") (class "Default")
      (node (ref "J4") (pin "2") (pintype "power_in"))
    )
    (net (code "40") (name "unconnected-(PS1-DNC-Pad13)") (class "Default")
      (node (ref "PS1") (pin "13") (pinfunction "DNC_13") (pintype "passive+no_connect"))
    )
    (net (code "41") (name "unconnected-(U3-NC-Pad3)") (class "Default")
      (node (ref "U3") (pin "3") (pinfunction "NC_3") (pintype "passive+no_connect"))
    )
    (net (code "42") (name "unconnected-(U13-NC-Pad6)") (class "Default")
      (node (ref "U13") (pin "6") (pinfunction "NC_6") (pintype "passive+no_connect"))
    )
  )
)
